# adv_block.net
KiCad netlist of a schematic drawn in Altium Designer
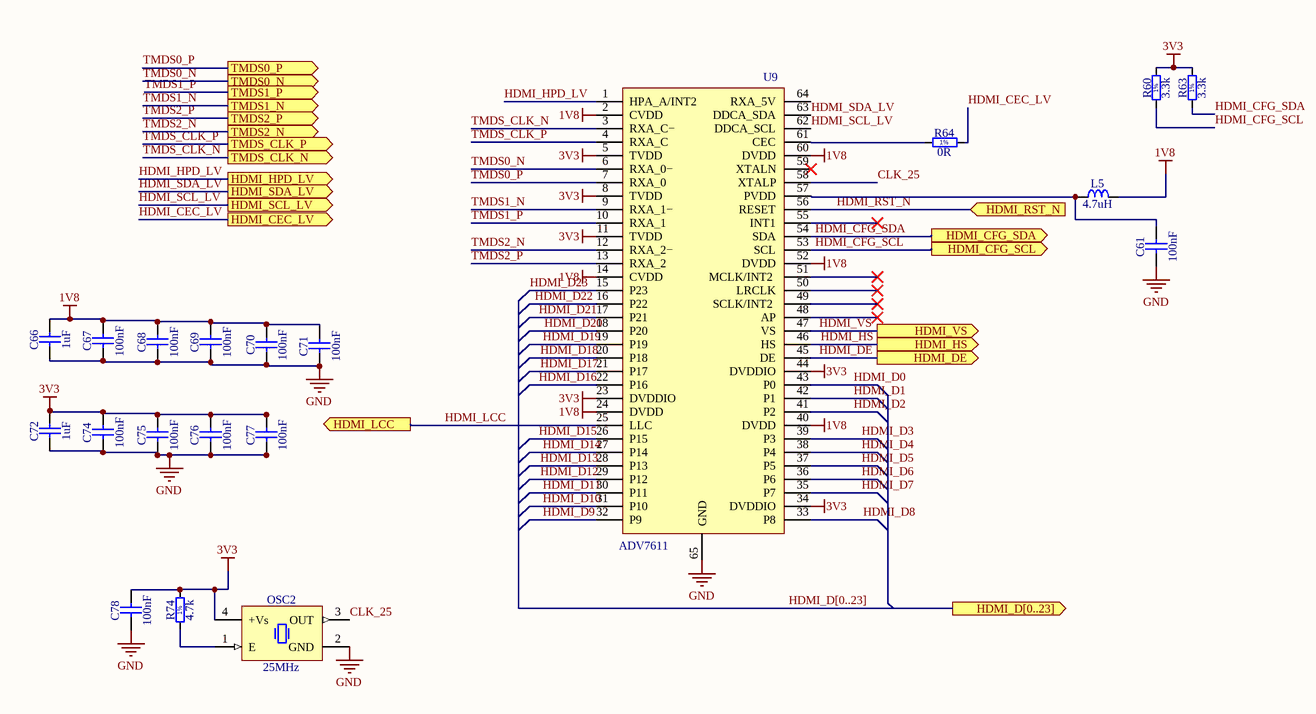
[diagram p0: adv_block.SchDoc]

(export (version "E")
  (design (tool "Eeschema 10.0.6"))
  (components
    (comp (ref "C61")
      (value "100nF")
      (footprint "CAPC1005X55N")
      (description "Non-polarised capacitor")
      (fields
        (field (name "PART NUMBER") "CC0402_100NF_16V_10%_X5R")
        (field (name "VOLTAGE") "16V")
        (field (name "AUTHOR") "CERN DEM JLC")
      )
      (libsource (lib "Capacitors") (part "Capacitor - non polarized"))
    )
    (comp (ref "C66")
      (value "1uF")
      (footprint "CAPC1005X55N")
      (description "Non-polarised capacitor")
      (fields
        (field (name "PART NUMBER") "CC0402_100NF_16V_10%_X5R")
        (field (name "VOLTAGE") "16V")
        (field (name "AUTHOR") "CERN DEM JLC")
      )
      (libsource (lib "Capacitors") (part "Capacitor - non polarized"))
    )
    (comp (ref "C67")
      (value "100nF")
      (footprint "CAPC1005X55N")
      (description "Non-polarised capacitor")
      (fields
        (field (name "PART NUMBER") "CC0402_100NF_16V_10%_X5R")
        (field (name "VOLTAGE") "16V")
        (field (name "AUTHOR") "CERN DEM JLC")
      )
      (libsource (lib "Capacitors") (part "Capacitor - non polarized"))
    )
    (comp (ref "C68")
      (value "100nF")
      (footprint "CAPC1005X55N")
      (description "Non-polarised capacitor")
      (fields
        (field (name "PART NUMBER") "CC0402_100NF_16V_10%_X5R")
        (field (name "VOLTAGE") "16V")
        (field (name "AUTHOR") "CERN DEM JLC")
      )
      (libsource (lib "Capacitors") (part "Capacitor - non polarized"))
    )
    (comp (ref "C69")
      (value "100nF")
      (footprint "CAPC1005X55N")
      (description "Non-polarised capacitor")
      (fields
        (field (name "PART NUMBER") "CC0402_100NF_16V_10%_X5R")
        (field (name "VOLTAGE") "16V")
        (field (name "AUTHOR") "CERN DEM JLC")
      )
      (libsource (lib "Capacitors") (part "Capacitor - non polarized"))
    )
    (comp (ref "C70")
      (value "100nF")
      (footprint "CAPC1005X55N")
      (description "Non-polarised capacitor")
      (fields
        (field (name "PART NUMBER") "CC0402_100NF_16V_10%_X5R")
        (field (name "VOLTAGE") "16V")
        (field (name "AUTHOR") "CERN DEM JLC")
      )
      (libsource (lib "Capacitors") (part "Capacitor - non polarized"))
    )
    (comp (ref "C71")
      (value "100nF")
      (footprint "CAPC1005X55N")
      (description "Non-polarised capacitor")
      (fields
        (field (name "PART NUMBER") "CC0402_100NF_16V_10%_X5R")
        (field (name "VOLTAGE") "16V")
        (field (name "AUTHOR") "CERN DEM JLC")
      )
      (libsource (lib "Capacitors") (part "Capacitor - non polarized"))
    )
    (comp (ref "C72")
      (value "1uF")
      (footprint "CAPC1005X55N")
      (description "Non-polarised capacitor")
      (fields
        (field (name "PART NUMBER") "CC0402_100NF_16V_10%_X5R")
        (field (name "VOLTAGE") "16V")
        (field (name "AUTHOR") "CERN DEM JLC")
      )
      (libsource (lib "Capacitors") (part "Capacitor - non polarized"))
    )
    (comp (ref "C74")
      (value "100nF")
      (footprint "CAPC1005X55N")
      (description "Non-polarised capacitor")
      (fields
        (field (name "PART NUMBER") "CC0402_100NF_16V_10%_X5R")
        (field (name "VOLTAGE") "16V")
        (field (name "AUTHOR") "CERN DEM JLC")
      )
      (libsource (lib "Capacitors") (part "Capacitor - non polarized"))
    )
    (comp (ref "C75")
      (value "100nF")
      (footprint "CAPC1005X55N")
      (description "Non-polarised capacitor")
      (fields
        (field (name "PART NUMBER") "CC0402_100NF_16V_10%_X5R")
        (field (name "VOLTAGE") "16V")
        (field (name "AUTHOR") "CERN DEM JLC")
      )
      (libsource (lib "Capacitors") (part "Capacitor - non polarized"))
    )
    (comp (ref "C76")
      (value "100nF")
      (footprint "CAPC1005X55N")
      (description "Non-polarised capacitor")
      (fields
        (field (name "PART NUMBER") "CC0402_100NF_16V_10%_X5R")
        (field (name "VOLTAGE") "16V")
        (field (name "AUTHOR") "CERN DEM JLC")
      )
      (libsource (lib "Capacitors") (part "Capacitor - non polarized"))
    )
    (comp (ref "C77")
      (value "100nF")
      (footprint "CAPC1005X55N")
      (description "Non-polarised capacitor")
      (fields
        (field (name "PART NUMBER") "CC0402_100NF_16V_10%_X5R")
        (field (name "VOLTAGE") "16V")
        (field (name "AUTHOR") "CERN DEM JLC")
      )
      (libsource (lib "Capacitors") (part "Capacitor - non polarized"))
    )
    (comp (ref "C78")
      (value "100nF")
      (footprint "CAPC1005X55N")
      (description "Non-polarised capacitor")
      (fields
        (field (name "PART NUMBER") "CC0402_100NF_16V_10%_X5R")
        (field (name "VOLTAGE") "16V")
        (field (name "AUTHOR") "CERN DEM JLC")
      )
      (libsource (lib "Capacitors") (part "Capacitor - non polarized"))
    )
    (comp (ref "L5")
      (value "4.7uH")
      (footprint "IND_MURATA_BLM31PG")
      (description "Inductor")
      (fields
        (field (name "PART NUMBER") "IND1206_MURATA_BLM31PG500SN1")
        (field (name "POWER") "3.5A")
        (field (name "AUTHOR") "CERN DEM JLC")
      )
      (libsource (lib "Inductors & Transformers") (part "Inductor"))
    )
    (comp (ref "OSC2")
      (value "25MHz")
      (footprint "OSC_IQD_CFPS-69")
      (description "Oscillator 4 pins 1=E 2=GND 3=OUT 4=+Vs")
      (fields
        (field (name "PART NUMBER") "OSC_50MHZ_IQD_LFSPXO009592")
        (field (name "MANUFACTURER") "IQD FREQUENCY PRODUCTS")
        (field (name "AUTHOR") "CERN DEM JLC")
      )
      (libsource (lib "ICs And Semiconductors") (part "Oscillator 1E 2GND 3OUT 4Vs"))
    )
    (comp (ref "R60")
      (value "3.3k")
      (footprint "RESC1005X40N")
      (description "Resistor - 1%")
      (fields
        (field (name "PART NUMBER") "R0402_10K_1%_0.0625W_100PPM")
        (field (name "POWER") "0.0625W")
        (field (name "AUTHOR") "CERN DEM JLC")
      )
      (libsource (lib "Resistors") (part "Resistor - 1%"))
    )
    (comp (ref "R63")
      (value "3.3k")
      (footprint "RESC1005X40N")
      (description "Resistor - 1%")
      (fields
        (field (name "PART NUMBER") "R0402_10K_1%_0.0625W_100PPM")
        (field (name "POWER") "0.0625W")
        (field (name "AUTHOR") "CERN DEM JLC")
      )
      (libsource (lib "Resistors") (part "Resistor - 1%"))
    )
    (comp (ref "R64")
      (value "0R")
      (footprint "RESC1005X40N")
      (description "Resistor - 1%")
      (fields
        (field (name "PART NUMBER") "R0402_10K_1%_0.0625W_100PPM")
        (field (name "POWER") "0.0625W")
        (field (name "AUTHOR") "CERN DEM JLC")
      )
      (libsource (lib "Resistors") (part "Resistor - 1%"))
    )
    (comp (ref "R74")
      (value "4.7k")
      (footprint "RESC1608X55N")
      (description "Resistor - 1%")
      (fields
        (field (name "PART NUMBER") "R0603_100K_1%_0.1W_100PPM")
        (field (name "POWER") "0.1W")
        (field (name "AUTHOR") "CERN DEM JLC")
      )
      (libsource (lib "Resistors") (part "Resistor - 1%"))
    )
    (comp (ref "U9")
      (value "ADV7611")
      (footprint "QFP50P1200X1200X120-65N-S415")
      (description "Low Power 165 MHz HDMI Receiver")
      (libsource (lib "lib") (part "ADV7611"))
    )
  )
  (nets
    (net (code "1") (name "/CLK_25") (class "Default")
      (node (ref "OSC2") (pin "3") (pinfunction "OUT_3") (pintype "output"))
      (node (ref "U9") (pin "58") (pinfunction "XTALP_58") (pintype "passive"))
    )
    (net (code "2") (name "/HDMI_CEC_LV") (class "Default")
      (node (ref "R64") (pin "2") (pinfunction "2_2") (pintype "passive"))
    )
    (net (code "3") (name "/HDMI_CFG_SCL") (class "Default")
      (node (ref "R60") (pin "1") (pinfunction "1_1") (pintype "passive"))
      (node (ref "U9") (pin "53") (pinfunction "SCL_53") (pintype "passive"))
    )
    (net (code "4") (name "/HDMI_CFG_SDA") (class "Default")
      (node (ref "R63") (pin "1") (pinfunction "1_1") (pintype "passive"))
      (node (ref "U9") (pin "54") (pinfunction "SDA_54") (pintype "passive"))
    )
    (net (code "5") (name "/HDMI_D0") (class "Default")
      (node (ref "U9") (pin "43") (pinfunction "P0_43") (pintype "passive"))
    )
    (net (code "6") (name "/HDMI_D1") (class "Default")
      (node (ref "U9") (pin "42") (pinfunction "P1_42") (pintype "passive"))
    )
    (net (code "7") (name "/HDMI_D2") (class "Default")
      (node (ref "U9") (pin "41") (pinfunction "P2_41") (pintype "passive"))
    )
    (net (code "8") (name "/HDMI_D3") (class "Default")
      (node (ref "U9") (pin "39") (pinfunction "P3_39") (pintype "passive"))
    )
    (net (code "9") (name "/HDMI_D4") (class "Default")
      (node (ref "U9") (pin "38") (pinfunction "P4_38") (pintype "passive"))
    )
    (net (code "10") (name "/HDMI_D5") (class "Default")
      (node (ref "U9") (pin "37") (pinfunction "P5_37") (pintype "passive"))
    )
    (net (code "11") (name "/HDMI_D6") (class "Default")
      (node (ref "U9") (pin "36") (pinfunction "P6_36") (pintype "passive"))
    )
    (net (code "12") (name "/HDMI_D7") (class "Default")
      (node (ref "U9") (pin "35") (pinfunction "P7_35") (pintype "passive"))
    )
    (net (code "13") (name "/HDMI_D8") (class "Default")
      (node (ref "U9") (pin "33") (pinfunction "P8_33") (pintype "passive"))
    )
    (net (code "14") (name "/HDMI_D9") (class "Default")
      (node (ref "U9") (pin "32") (pinfunction "P9_32") (pintype "passive"))
    )
    (net (code "15") (name "/HDMI_D10") (class "Default")
      (node (ref "U9") (pin "31") (pinfunction "P10_31") (pintype "passive"))
    )
    (net (code "16") (name "/HDMI_D11") (class "Default")
      (node (ref "U9") (pin "30") (pinfunction "P11_30") (pintype "passive"))
    )
    (net (code "17") (name "/HDMI_D12") (class "Default")
      (node (ref "U9") (pin "29") (pinfunction "P12_29") (pintype "passive"))
    )
    (net (code "18") (name "/HDMI_D13") (class "Default")
      (node (ref "U9") (pin "28") (pinfunction "P13_28") (pintype "passive"))
    )
    (net (code "19") (name "/HDMI_D14") (class "Default")
      (node (ref "U9") (pin "27") (pinfunction "P14_27") (pintype "passive"))
    )
    (net (code "20") (name "/HDMI_D15") (class "Default")
      (node (ref "U9") (pin "26") (pinfunction "P15_26") (pintype "passive"))
    )
    (net (code "21") (name "/HDMI_D16") (class "Default")
      (node (ref "U9") (pin "22") (pinfunction "P16_22") (pintype "passive"))
    )
    (net (code "22") (name "/HDMI_D17") (class "Default")
      (node (ref "U9") (pin "21") (pinfunction "P17_21") (pintype "passive"))
    )
    (net (code "23") (name "/HDMI_D18") (class "Default")
      (node (ref "U9") (pin "20") (pinfunction "P18_20") (pintype "passive"))
    )
    (net (code "24") (name "/HDMI_D19") (class "Default")
      (node (ref "U9") (pin "19") (pinfunction "P19_19") (pintype "passive"))
    )
    (net (code "25") (name "/HDMI_D20") (class "Default")
      (node (ref "U9") (pin "18") (pinfunction "P20_18") (pintype "passive"))
    )
    (net (code "26") (name "/HDMI_D21") (class "Default")
      (node (ref "U9") (pin "17") (pinfunction "P21_17") (pintype "passive"))
    )
    (net (code "27") (name "/HDMI_D22") (class "Default")
      (node (ref "U9") (pin "16") (pinfunction "P22_16") (pintype "passive"))
    )
    (net (code "28") (name "/HDMI_D23") (class "Default")
      (node (ref "U9") (pin "15") (pinfunction "P23_15") (pintype "passive"))
    )
    (net (code "29") (name "/HDMI_DE") (class "Default")
      (node (ref "U9") (pin "45") (pinfunction "DE_45") (pintype "passive"))
    )
    (net (code "31") (name "/HDMI_HPD_LV") (class "Default")
      (node (ref "U9") (pin "1") (pinfunction "HPA_A/INT2_1") (pintype "passive"))
    )
    (net (code "32") (name "/HDMI_HS") (class "Default")
      (node (ref "U9") (pin "46") (pinfunction "HS_46") (pintype "passive"))
    )
    (net (code "33") (name "/HDMI_LCC") (class "Default")
      (node (ref "U9") (pin "25") (pinfunction "LLC_25") (pintype "passive"))
    )
    (net (code "34") (name "/HDMI_RST_N") (class "Default")
      (node (ref "U9") (pin "56") (pinfunction "RESET_56") (pintype "passive"))
    )
    (net (code "35") (name "/HDMI_SCL_LV") (class "Default")
      (node (ref "U9") (pin "62") (pinfunction "DDCA_SCL_62") (pintype "passive"))
    )
    (net (code "36") (name "/HDMI_SDA_LV") (class "Default")
      (node (ref "U9") (pin "63") (pinfunction "DDCA_SDA_63") (pintype "passive"))
    )
    (net (code "37") (name "/HDMI_VS") (class "Default")
      (node (ref "U9") (pin "47") (pinfunction "VS_47") (pintype "passive"))
    )
    (net (code "38") (name "/TMDS0_N") (class "Default")
      (node (ref "U9") (pin "6") (pinfunction "RXA_0−_6") (pintype "passive"))
    )
    (net (code "39") (name "/TMDS0_P") (class "Default")
      (node (ref "U9") (pin "7") (pinfunction "RXA_0_7") (pintype "passive"))
    )
    (net (code "40") (name "/TMDS1_N") (class "Default")
      (node (ref "U9") (pin "9") (pinfunction "RXA_1−_9") (pintype "passive"))
    )
    (net (code "41") (name "/TMDS1_P") (class "Default")
      (node (ref "U9") (pin "10") (pinfunction "RXA_1_10") (pintype "passive"))
    )
    (net (code "42") (name "/TMDS2_N") (class "Default")
      (node (ref "U9") (pin "12") (pinfunction "RXA_2−_12") (pintype "passive"))
    )
    (net (code "43") (name "/TMDS2_P") (class "Default")
      (node (ref "U9") (pin "13") (pinfunction "RXA_2_13") (pintype "passive"))
    )
    (net (code "44") (name "/TMDS_CLK_N") (class "Default")
      (node (ref "U9") (pin "3") (pinfunction "RXA_C−_3") (pintype "passive"))
    )
    (net (code "45") (name "/TMDS_CLK_P") (class "Default")
      (node (ref "U9") (pin "4") (pinfunction "RXA_C_4") (pintype "passive"))
    )
    (net (code "46") (name "1V8") (class "Default")
      (node (ref "C66") (pin "2") (pinfunction "2_2") (pintype "passive"))
      (node (ref "C67") (pin "2") (pinfunction "2_2") (pintype "passive"))
      (node (ref "C68") (pin "2") (pinfunction "2_2") (pintype "passive"))
      (node (ref "C69") (pin "2") (pinfunction "2_2") (pintype "passive"))
      (node (ref "C70") (pin "2") (pinfunction "2_2") (pintype "passive"))
      (node (ref "C71") (pin "2") (pinfunction "2_2") (pintype "passive"))
      (node (ref "L5") (pin "2") (pinfunction "2_2") (pintype "passive"))
      (node (ref "U9") (pin "14") (pinfunction "CVDD_14") (pintype "passive"))
      (node (ref "U9") (pin "2") (pinfunction "CVDD_2") (pintype "passive"))
      (node (ref "U9") (pin "24") (pinfunction "DVDD_24") (pintype "passive"))
      (node (ref "U9") (pin "40") (pinfunction "DVDD_40") (pintype "passive"))
      (node (ref "U9") (pin "52") (pinfunction "DVDD_52") (pintype "passive"))
      (node (ref "U9") (pin "60") (pinfunction "DVDD_60") (pintype "passive"))
    )
    (net (code "47") (name "3V3") (class "Default")
      (node (ref "C72") (pin "2") (pinfunction "2_2") (pintype "passive"))
      (node (ref "C74") (pin "2") (pinfunction "2_2") (pintype "passive"))
      (node (ref "C75") (pin "2") (pinfunction "2_2") (pintype "passive"))
      (node (ref "C76") (pin "2") (pinfunction "2_2") (pintype "passive"))
      (node (ref "C77") (pin "2") (pinfunction "2_2") (pintype "passive"))
      (node (ref "C78") (pin "2") (pinfunction "2_2") (pintype "passive"))
      (node (ref "OSC2") (pin "4") (pinfunction "+Vs_4") (pintype "power_in"))
      (node (ref "R60") (pin "2") (pinfunction "2_2") (pintype "passive"))
      (node (ref "R63") (pin "2") (pinfunction "2_2") (pintype "passive"))
      (node (ref "R74") (pin "2") (pinfunction "2_2") (pintype "passive"))
      (node (ref "U9") (pin "11") (pinfunction "TVDD_11") (pintype "passive"))
      (node (ref "U9") (pin "23") (pinfunction "DVDDIO_23") (pintype "passive"))
      (node (ref "U9") (pin "34") (pinfunction "DVDDIO_34") (pintype "passive"))
      (node (ref "U9") (pin "44") (pinfunction "DVDDIO_44") (pintype "passive"))
      (node (ref "U9") (pin "5") (pinfunction "TVDD_5") (pintype "passive"))
      (node (ref "U9") (pin "8") (pinfunction "TVDD_8") (pintype "passive"))
    )
    (net (code "48") (name "GND") (class "Default")
      (node (ref "C61") (pin "1") (pinfunction "1_1") (pintype "passive"))
      (node (ref "C66") (pin "1") (pinfunction "1_1") (pintype "passive"))
      (node (ref "C67") (pin "1") (pinfunction "1_1") (pintype "passive"))
      (node (ref "C68") (pin "1") (pinfunction "1_1") (pintype "passive"))
      (node (ref "C69") (pin "1") (pinfunction "1_1") (pintype "passive"))
      (node (ref "C70") (pin "1") (pinfunction "1_1") (pintype "passive"))
      (node (ref "C71") (pin "1") (pinfunction "1_1") (pintype "passive"))
      (node (ref "C72") (pin "1") (pinfunction "1_1") (pintype "passive"))
      (node (ref "C74") (pin "1") (pinfunction "1_1") (pintype "passive"))
      (node (ref "C75") (pin "1") (pinfunction "1_1") (pintype "passive"))
      (node (ref "C76") (pin "1") (pinfunction "1_1") (pintype "passive"))
      (node (ref "C77") (pin "1") (pinfunction "1_1") (pintype "passive"))
      (node (ref "C78") (pin "1") (pinfunction "1_1") (pintype "passive"))
      (node (ref "OSC2") (pin "2") (pinfunction "GND_2") (pintype "power_in"))
      (node (ref "U9") (pin "65") (pinfunction "GND_65") (pintype "passive"))
    )
    (net (code "49") (name "Net-(OSC2-E)") (class "Default")
      (node (ref "OSC2") (pin "1") (pinfunction "E_1") (pintype "input"))
      (node (ref "R74") (pin "1") (pinfunction "1_1") (pintype "passive"))
    )
    (net (code "50") (name "Net-(U9-CEC)") (class "Default")
      (node (ref "R64") (pin "1") (pinfunction "1_1") (pintype "passive"))
      (node (ref "U9") (pin "61") (pinfunction "CEC_61") (pintype "passive"))
    )
    (net (code "51") (name "Net-(U9-PVDD)") (class "Default")
      (node (ref "C61") (pin "2") (pinfunction "2_2") (pintype "passive"))
      (node (ref "L5") (pin "1") (pinfunction "1_1") (pintype "passive"))
      (node (ref "U9") (pin "57") (pinfunction "PVDD_57") (pintype "passive"))
    )
    (net (code "52") (name "unconnected-(U9-AP-Pad48)") (class "Default")
      (node (ref "U9") (pin "48") (pinfunction "AP_48") (pintype "passive+no_connect"))
    )
    (net (code "53") (name "unconnected-(U9-INT1-Pad55)") (class "Default")
      (node (ref "U9") (pin "55") (pinfunction "INT1_55") (pintype "passive+no_connect"))
    )
    (net (code "54") (name "unconnected-(U9-LRCLK-Pad50)") (class "Default")
      (node (ref "U9") (pin "50") (pinfunction "LRCLK_50") (pintype "passive+no_connect"))
    )
    (net (code "55") (name "unconnected-(U9-MCLK{slash}INT2-Pad51)") (class "Default")
      (node (ref "U9") (pin "51") (pinfunction "MCLK/INT2_51") (pintype "passive+no_connect"))
    )
    (net (code "56") (name "unconnected-(U9-RXA_5V-Pad64)") (class "Default")
      (node (ref "U9") (pin "64") (pinfunction "RXA_5V_64") (pintype "passive"))
    )
    (net (code "57") (name "unconnected-(U9-SCLK{slash}INT2-Pad49)") (class "Default")
      (node (ref "U9") (pin "49") (pinfunction "SCLK/INT2_49") (pintype "passive+no_connect"))
    )
    (net (code "58") (name "unconnected-(U9-XTALN-Pad59)") (class "Default")
      (node (ref "U9") (pin "59") (pinfunction "XTALN_59") (pintype "passive+no_connect"))
    )
  )
)
